# Batt_Op_Amp.net
KiCad netlist of a schematic drawn in Altium Designer
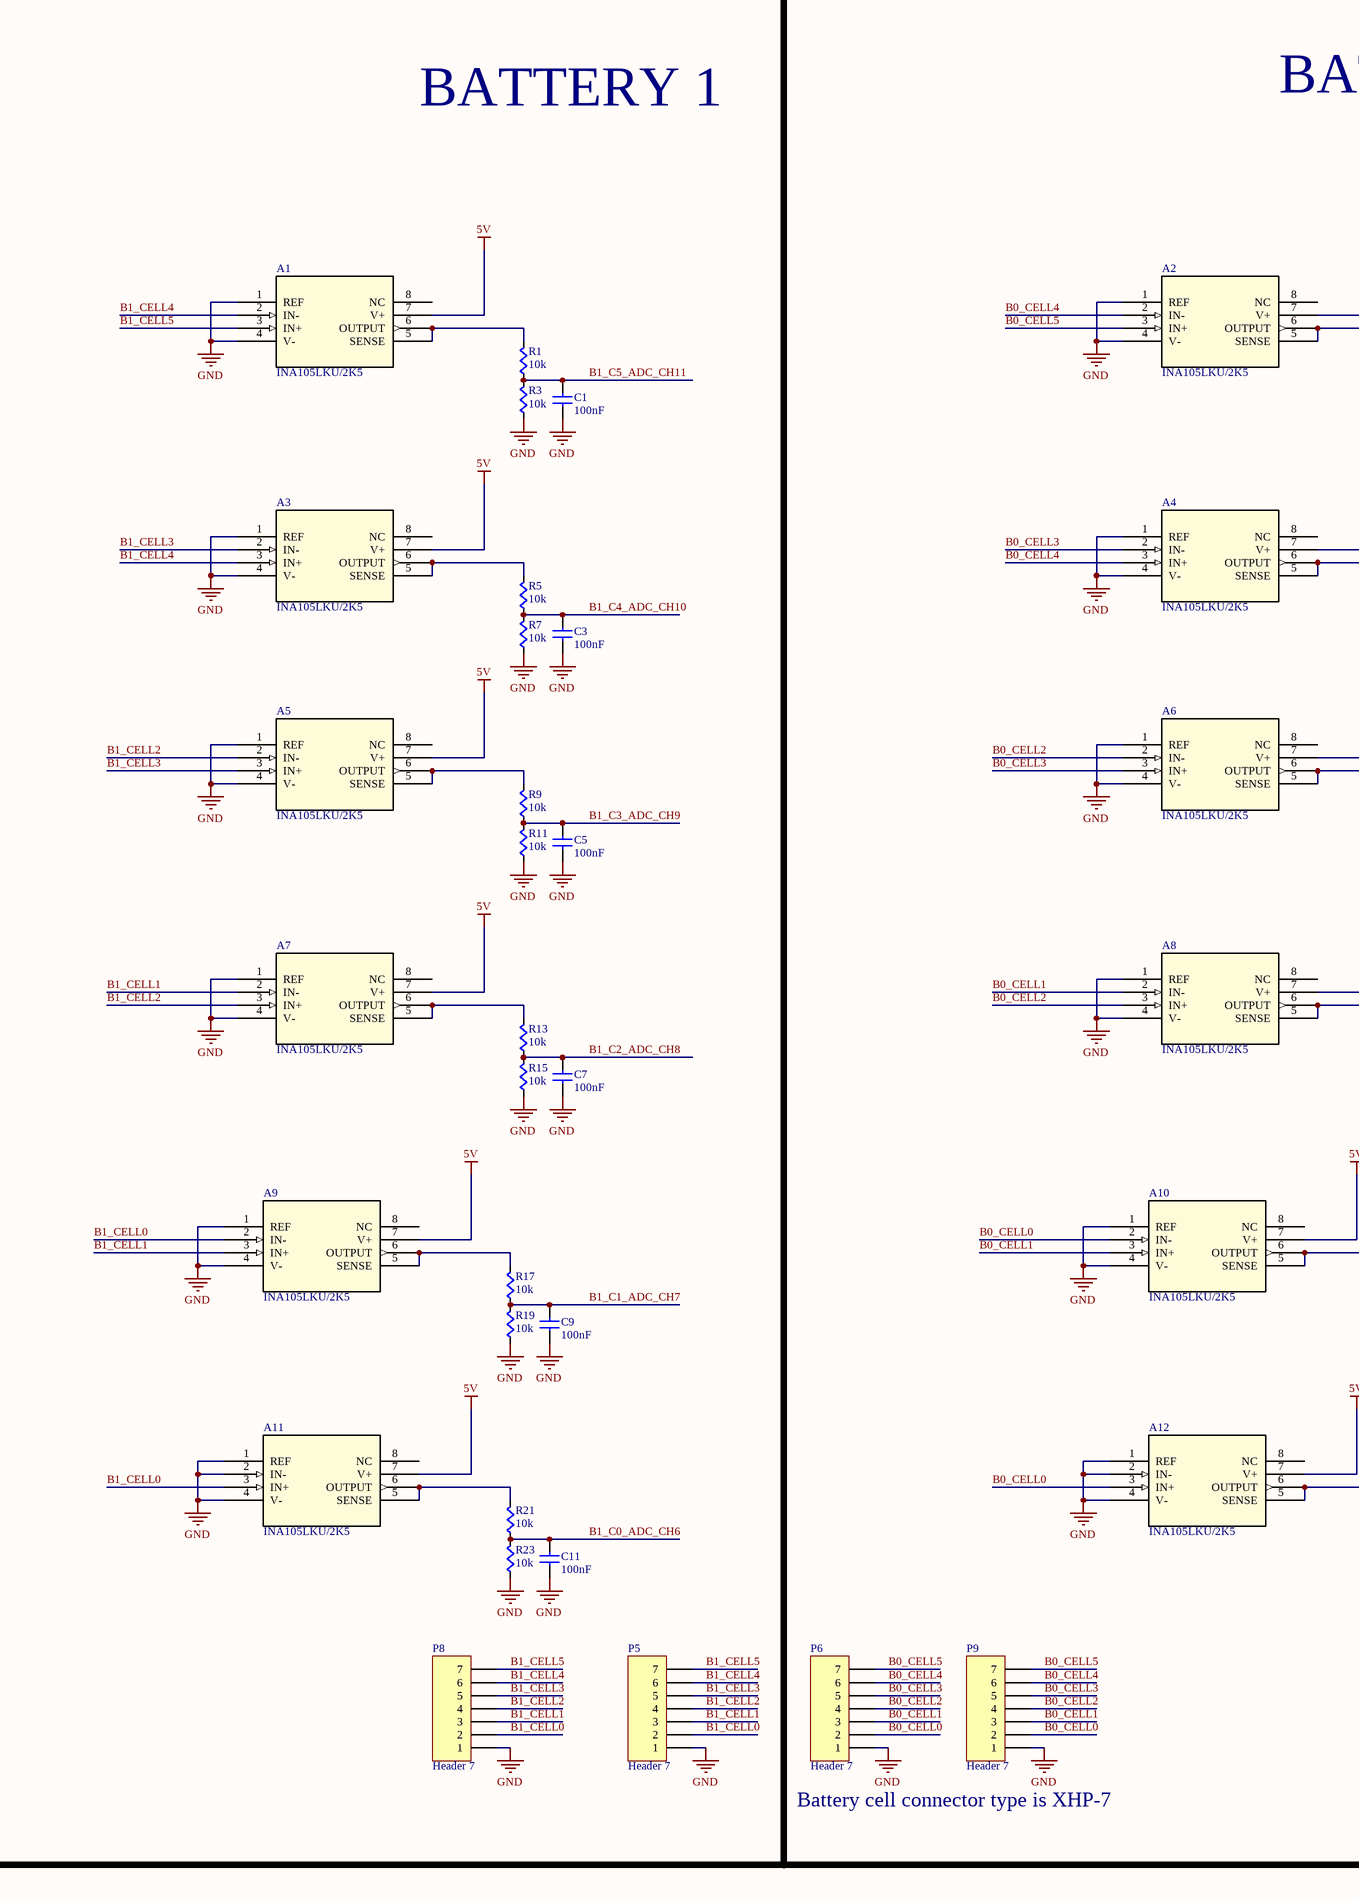
[diagram p0: Batt_Op_Amp.SchDoc, left]
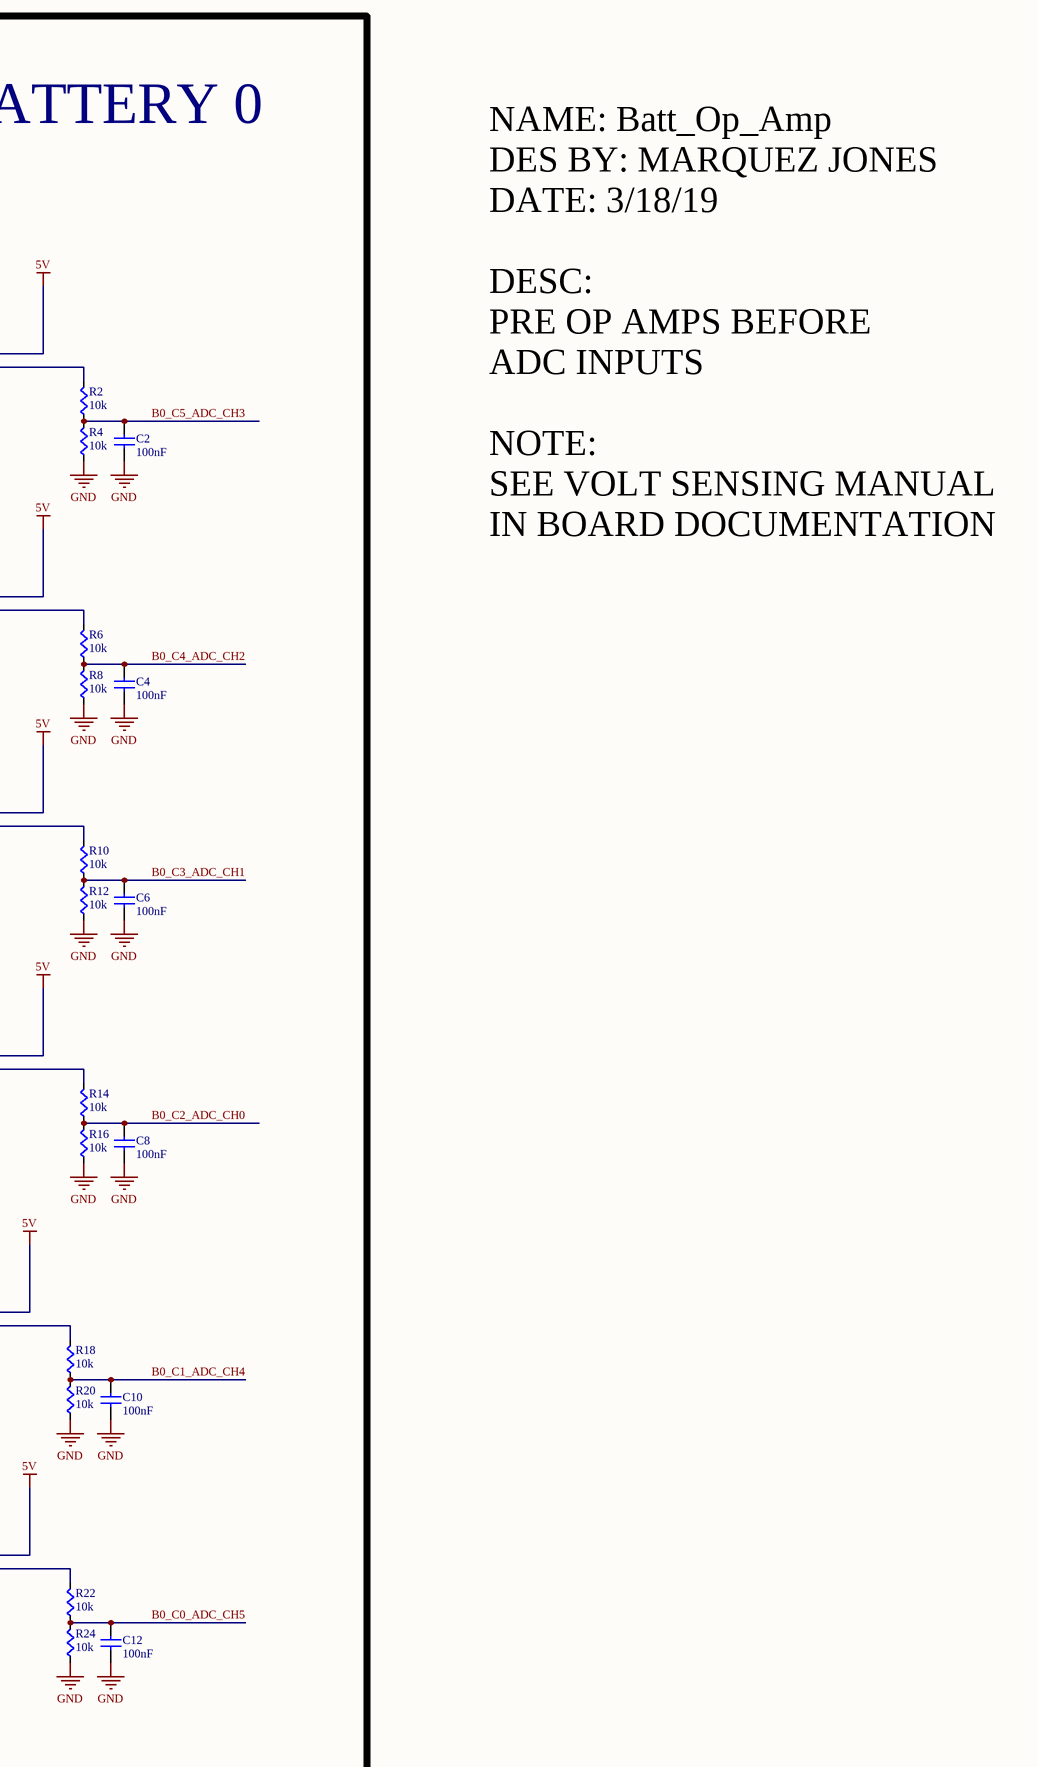
[diagram p1: Batt_Op_Amp.SchDoc, right]

(export (version "E")
  (design (tool "Eeschema 10.0.6"))
  (components
    (comp (ref "A1")
      (value "INA105LKU/2K5")
      (footprint "SOIC-8N")
      (libsource (lib "ICs") (part "INA105LKU/2K5"))
    )
    (comp (ref "A2")
      (value "INA105LKU/2K5")
      (footprint "SOIC-8N")
      (libsource (lib "ICs") (part "INA105LKU/2K5"))
    )
    (comp (ref "A3")
      (value "INA105LKU/2K5")
      (footprint "SOIC-8N")
      (libsource (lib "ICs") (part "INA105LKU/2K5"))
    )
    (comp (ref "A4")
      (value "INA105LKU/2K5")
      (footprint "SOIC-8N")
      (libsource (lib "ICs") (part "INA105LKU/2K5"))
    )
    (comp (ref "A5")
      (value "INA105LKU/2K5")
      (footprint "SOIC-8N")
      (libsource (lib "ICs") (part "INA105LKU/2K5"))
    )
    (comp (ref "A6")
      (value "INA105LKU/2K5")
      (footprint "SOIC-8N")
      (libsource (lib "ICs") (part "INA105LKU/2K5"))
    )
    (comp (ref "A7")
      (value "INA105LKU/2K5")
      (footprint "SOIC-8N")
      (libsource (lib "ICs") (part "INA105LKU/2K5"))
    )
    (comp (ref "A8")
      (value "INA105LKU/2K5")
      (footprint "SOIC-8N")
      (libsource (lib "ICs") (part "INA105LKU/2K5"))
    )
    (comp (ref "A9")
      (value "INA105LKU/2K5")
      (footprint "SOIC-8N")
      (libsource (lib "ICs") (part "INA105LKU/2K5"))
    )
    (comp (ref "A10")
      (value "INA105LKU/2K5")
      (footprint "SOIC-8N")
      (libsource (lib "ICs") (part "INA105LKU/2K5"))
    )
    (comp (ref "A11")
      (value "INA105LKU/2K5")
      (footprint "SOIC-8N")
      (libsource (lib "ICs") (part "INA105LKU/2K5"))
    )
    (comp (ref "A12")
      (value "INA105LKU/2K5")
      (footprint "SOIC-8N")
      (libsource (lib "ICs") (part "INA105LKU/2K5"))
    )
    (comp (ref "C1")
      (value "100nF")
      (footprint "CAPC0603")
      (fields (field (name "Comment") "Cap"))
      (libsource (lib "Passives") (part "Cap"))
    )
    (comp (ref "C2")
      (value "100nF")
      (footprint "CAPC0603")
      (fields (field (name "Comment") "Cap"))
      (libsource (lib "Passives") (part "Cap"))
    )
    (comp (ref "C3")
      (value "100nF")
      (footprint "CAPC0603")
      (fields (field (name "Comment") "Cap"))
      (libsource (lib "Passives") (part "Cap"))
    )
    (comp (ref "C4")
      (value "100nF")
      (footprint "CAPC0603")
      (fields (field (name "Comment") "Cap"))
      (libsource (lib "Passives") (part "Cap"))
    )
    (comp (ref "C5")
      (value "100nF")
      (footprint "CAPC0603")
      (fields (field (name "Comment") "Cap"))
      (libsource (lib "Passives") (part "Cap"))
    )
    (comp (ref "C6")
      (value "100nF")
      (footprint "CAPC0603")
      (fields (field (name "Comment") "Cap"))
      (libsource (lib "Passives") (part "Cap"))
    )
    (comp (ref "C7")
      (value "100nF")
      (footprint "CAPC0603")
      (fields (field (name "Comment") "Cap"))
      (libsource (lib "Passives") (part "Cap"))
    )
    (comp (ref "C8")
      (value "100nF")
      (footprint "CAPC0603")
      (fields (field (name "Comment") "Cap"))
      (libsource (lib "Passives") (part "Cap"))
    )
    (comp (ref "C9")
      (value "100nF")
      (footprint "CAPC0603")
      (fields (field (name "Comment") "Cap"))
      (libsource (lib "Passives") (part "Cap"))
    )
    (comp (ref "C10")
      (value "100nF")
      (footprint "CAPC0603")
      (fields (field (name "Comment") "Cap"))
      (libsource (lib "Passives") (part "Cap"))
    )
    (comp (ref "C11")
      (value "100nF")
      (footprint "CAPC0603")
      (fields (field (name "Comment") "Cap"))
      (libsource (lib "Passives") (part "Cap"))
    )
    (comp (ref "C12")
      (value "100nF")
      (footprint "CAPC0603")
      (fields (field (name "Comment") "Cap"))
      (libsource (lib "Passives") (part "Cap"))
    )
    (comp (ref "P5")
      (value "Header 7")
      (footprint "HDR1X7")
      (description "Header, 7-Pin")
      (fields (field (name "PUBLISHER") "Altium Limited"))
      (libsource (lib "Miscellaneous Connectors") (part "Header 7"))
    )
    (comp (ref "P6")
      (value "Header 7")
      (footprint "HDR1X7")
      (description "Header, 7-Pin")
      (fields (field (name "PUBLISHER") "Altium Limited"))
      (libsource (lib "Miscellaneous Connectors") (part "Header 7"))
    )
    (comp (ref "P8")
      (value "Header 7")
      (footprint "HDR1X7")
      (description "Header, 7-Pin")
      (fields (field (name "PUBLISHER") "Altium Limited"))
      (libsource (lib "Miscellaneous Connectors") (part "Header 7"))
    )
    (comp (ref "P9")
      (value "Header 7")
      (footprint "HDR1X7")
      (description "Header, 7-Pin")
      (fields (field (name "PUBLISHER") "Altium Limited"))
      (libsource (lib "Miscellaneous Connectors") (part "Header 7"))
    )
    (comp (ref "R1")
      (value "10k")
      (footprint "RES0603")
      (fields (field (name "Comment") "Res"))
      (libsource (lib "Passives") (part "Res"))
    )
    (comp (ref "R2")
      (value "10k")
      (footprint "RES0603")
      (fields (field (name "Comment") "Res"))
      (libsource (lib "Passives") (part "Res"))
    )
    (comp (ref "R3")
      (value "10k")
      (footprint "RES0603")
      (fields (field (name "Comment") "Res"))
      (libsource (lib "Passives") (part "Res"))
    )
    (comp (ref "R4")
      (value "10k")
      (footprint "RES0603")
      (fields (field (name "Comment") "Res"))
      (libsource (lib "Passives") (part "Res"))
    )
    (comp (ref "R5")
      (value "10k")
      (footprint "RES0603")
      (fields (field (name "Comment") "Res"))
      (libsource (lib "Passives") (part "Res"))
    )
    (comp (ref "R6")
      (value "10k")
      (footprint "RES0603")
      (fields (field (name "Comment") "Res"))
      (libsource (lib "Passives") (part "Res"))
    )
    (comp (ref "R7")
      (value "10k")
      (footprint "RES0603")
      (fields (field (name "Comment") "Res"))
      (libsource (lib "Passives") (part "Res"))
    )
    (comp (ref "R8")
      (value "10k")
      (footprint "RES0603")
      (fields (field (name "Comment") "Res"))
      (libsource (lib "Passives") (part "Res"))
    )
    (comp (ref "R9")
      (value "10k")
      (footprint "RES0603")
      (fields (field (name "Comment") "Res"))
      (libsource (lib "Passives") (part "Res"))
    )
    (comp (ref "R10")
      (value "10k")
      (footprint "RES0603")
      (fields (field (name "Comment") "Res"))
      (libsource (lib "Passives") (part "Res"))
    )
    (comp (ref "R11")
      (value "10k")
      (footprint "RES0603")
      (fields (field (name "Comment") "Res"))
      (libsource (lib "Passives") (part "Res"))
    )
    (comp (ref "R12")
      (value "10k")
      (footprint "RES0603")
      (fields (field (name "Comment") "Res"))
      (libsource (lib "Passives") (part "Res"))
    )
    (comp (ref "R13")
      (value "10k")
      (footprint "RES0603")
      (fields (field (name "Comment") "Res"))
      (libsource (lib "Passives") (part "Res"))
    )
    (comp (ref "R14")
      (value "10k")
      (footprint "RES0603")
      (fields (field (name "Comment") "Res"))
      (libsource (lib "Passives") (part "Res"))
    )
    (comp (ref "R15")
      (value "10k")
      (footprint "RES0603")
      (fields (field (name "Comment") "Res"))
      (libsource (lib "Passives") (part "Res"))
    )
    (comp (ref "R16")
      (value "10k")
      (footprint "RES0603")
      (fields (field (name "Comment") "Res"))
      (libsource (lib "Passives") (part "Res"))
    )
    (comp (ref "R17")
      (value "10k")
      (footprint "RES0603")
      (fields (field (name "Comment") "Res"))
      (libsource (lib "Passives") (part "Res"))
    )
    (comp (ref "R18")
      (value "10k")
      (footprint "RES0603")
      (fields (field (name "Comment") "Res"))
      (libsource (lib "Passives") (part "Res"))
    )
    (comp (ref "R19")
      (value "10k")
      (footprint "RES0603")
      (fields (field (name "Comment") "Res"))
      (libsource (lib "Passives") (part "Res"))
    )
    (comp (ref "R20")
      (value "10k")
      (footprint "RES0603")
      (fields (field (name "Comment") "Res"))
      (libsource (lib "Passives") (part "Res"))
    )
    (comp (ref "R21")
      (value "10k")
      (footprint "RES0603")
      (fields (field (name "Comment") "Res"))
      (libsource (lib "Passives") (part "Res"))
    )
    (comp (ref "R22")
      (value "10k")
      (footprint "RES0603")
      (fields (field (name "Comment") "Res"))
      (libsource (lib "Passives") (part "Res"))
    )
    (comp (ref "R23")
      (value "10k")
      (footprint "RES0603")
      (fields (field (name "Comment") "Res"))
      (libsource (lib "Passives") (part "Res"))
    )
    (comp (ref "R24")
      (value "10k")
      (footprint "RES0603")
      (fields (field (name "Comment") "Res"))
      (libsource (lib "Passives") (part "Res"))
    )
  )
  (nets
    (net (code "1") (name "/B0_C0_ADC_CH5") (class "Default")
      (node (ref "C12") (pin "1") (pinfunction "A_1") (pintype "passive"))
      (node (ref "R22") (pin "2") (pinfunction "B_2") (pintype "passive"))
      (node (ref "R24") (pin "1") (pinfunction "A_1") (pintype "passive"))
    )
    (net (code "2") (name "/B0_C1_ADC_CH4") (class "Default")
      (node (ref "C10") (pin "1") (pinfunction "A_1") (pintype "passive"))
      (node (ref "R18") (pin "2") (pinfunction "B_2") (pintype "passive"))
      (node (ref "R20") (pin "1") (pinfunction "A_1") (pintype "passive"))
    )
    (net (code "3") (name "/B0_C2_ADC_CH0") (class "Default")
      (node (ref "C8") (pin "1") (pinfunction "A_1") (pintype "passive"))
      (node (ref "R14") (pin "2") (pinfunction "B_2") (pintype "passive"))
      (node (ref "R16") (pin "1") (pinfunction "A_1") (pintype "passive"))
    )
    (net (code "4") (name "/B0_C3_ADC_CH1") (class "Default")
      (node (ref "C6") (pin "1") (pinfunction "A_1") (pintype "passive"))
      (node (ref "R10") (pin "2") (pinfunction "B_2") (pintype "passive"))
      (node (ref "R12") (pin "1") (pinfunction "A_1") (pintype "passive"))
    )
    (net (code "5") (name "/B0_C4_ADC_CH2") (class "Default")
      (node (ref "C4") (pin "1") (pinfunction "A_1") (pintype "passive"))
      (node (ref "R6") (pin "2") (pinfunction "B_2") (pintype "passive"))
      (node (ref "R8") (pin "1") (pinfunction "A_1") (pintype "passive"))
    )
    (net (code "6") (name "/B0_C5_ADC_CH3") (class "Default")
      (node (ref "C2") (pin "1") (pinfunction "A_1") (pintype "passive"))
      (node (ref "R2") (pin "2") (pinfunction "B_2") (pintype "passive"))
      (node (ref "R4") (pin "1") (pinfunction "A_1") (pintype "passive"))
    )
    (net (code "7") (name "/B0_CELL0") (class "Default")
      (node (ref "A10") (pin "2") (pinfunction "IN-_2") (pintype "input"))
      (node (ref "A12") (pin "3") (pinfunction "IN+_3") (pintype "input"))
      (node (ref "P6") (pin "2") (pinfunction "2_2") (pintype "passive"))
      (node (ref "P9") (pin "2") (pinfunction "2_2") (pintype "passive"))
    )
    (net (code "8") (name "/B0_CELL1") (class "Default")
      (node (ref "A10") (pin "3") (pinfunction "IN+_3") (pintype "input"))
      (node (ref "A8") (pin "2") (pinfunction "IN-_2") (pintype "input"))
      (node (ref "P6") (pin "3") (pinfunction "3_3") (pintype "passive"))
      (node (ref "P9") (pin "3") (pinfunction "3_3") (pintype "passive"))
    )
    (net (code "9") (name "/B0_CELL2") (class "Default")
      (node (ref "A6") (pin "2") (pinfunction "IN-_2") (pintype "input"))
      (node (ref "A8") (pin "3") (pinfunction "IN+_3") (pintype "input"))
      (node (ref "P6") (pin "4") (pinfunction "4_4") (pintype "passive"))
      (node (ref "P9") (pin "4") (pinfunction "4_4") (pintype "passive"))
    )
    (net (code "10") (name "/B0_CELL3") (class "Default")
      (node (ref "A4") (pin "2") (pinfunction "IN-_2") (pintype "input"))
      (node (ref "A6") (pin "3") (pinfunction "IN+_3") (pintype "input"))
      (node (ref "P6") (pin "5") (pinfunction "5_5") (pintype "passive"))
      (node (ref "P9") (pin "5") (pinfunction "5_5") (pintype "passive"))
    )
    (net (code "11") (name "/B0_CELL4") (class "Default")
      (node (ref "A2") (pin "2") (pinfunction "IN-_2") (pintype "input"))
      (node (ref "A4") (pin "3") (pinfunction "IN+_3") (pintype "input"))
      (node (ref "P6") (pin "6") (pinfunction "6_6") (pintype "passive"))
      (node (ref "P9") (pin "6") (pinfunction "6_6") (pintype "passive"))
    )
    (net (code "12") (name "/B0_CELL5") (class "Default")
      (node (ref "A2") (pin "3") (pinfunction "IN+_3") (pintype "input"))
      (node (ref "P6") (pin "7") (pinfunction "7_7") (pintype "passive"))
      (node (ref "P9") (pin "7") (pinfunction "7_7") (pintype "passive"))
    )
    (net (code "13") (name "/B1_C0_ADC_CH6") (class "Default")
      (node (ref "C11") (pin "1") (pinfunction "A_1") (pintype "passive"))
      (node (ref "R21") (pin "2") (pinfunction "B_2") (pintype "passive"))
      (node (ref "R23") (pin "1") (pinfunction "A_1") (pintype "passive"))
    )
    (net (code "14") (name "/B1_C1_ADC_CH7") (class "Default")
      (node (ref "C9") (pin "1") (pinfunction "A_1") (pintype "passive"))
      (node (ref "R17") (pin "2") (pinfunction "B_2") (pintype "passive"))
      (node (ref "R19") (pin "1") (pinfunction "A_1") (pintype "passive"))
    )
    (net (code "15") (name "/B1_C2_ADC_CH8") (class "Default")
      (node (ref "C7") (pin "1") (pinfunction "A_1") (pintype "passive"))
      (node (ref "R13") (pin "2") (pinfunction "B_2") (pintype "passive"))
      (node (ref "R15") (pin "1") (pinfunction "A_1") (pintype "passive"))
    )
    (net (code "16") (name "/B1_C3_ADC_CH9") (class "Default")
      (node (ref "C5") (pin "1") (pinfunction "A_1") (pintype "passive"))
      (node (ref "R11") (pin "1") (pinfunction "A_1") (pintype "passive"))
      (node (ref "R9") (pin "2") (pinfunction "B_2") (pintype "passive"))
    )
    (net (code "17") (name "/B1_C4_ADC_CH10") (class "Default")
      (node (ref "C3") (pin "1") (pinfunction "A_1") (pintype "passive"))
      (node (ref "R5") (pin "2") (pinfunction "B_2") (pintype "passive"))
      (node (ref "R7") (pin "1") (pinfunction "A_1") (pintype "passive"))
    )
    (net (code "18") (name "/B1_C5_ADC_CH11") (class "Default")
      (node (ref "C1") (pin "1") (pinfunction "A_1") (pintype "passive"))
      (node (ref "R1") (pin "2") (pinfunction "B_2") (pintype "passive"))
      (node (ref "R3") (pin "1") (pinfunction "A_1") (pintype "passive"))
    )
    (net (code "19") (name "/B1_CELL0") (class "Default")
      (node (ref "A11") (pin "3") (pinfunction "IN+_3") (pintype "input"))
      (node (ref "A9") (pin "2") (pinfunction "IN-_2") (pintype "input"))
      (node (ref "P5") (pin "2") (pinfunction "2_2") (pintype "passive"))
      (node (ref "P8") (pin "2") (pinfunction "2_2") (pintype "passive"))
    )
    (net (code "20") (name "/B1_CELL1") (class "Default")
      (node (ref "A7") (pin "2") (pinfunction "IN-_2") (pintype "input"))
      (node (ref "A9") (pin "3") (pinfunction "IN+_3") (pintype "input"))
      (node (ref "P5") (pin "3") (pinfunction "3_3") (pintype "passive"))
      (node (ref "P8") (pin "3") (pinfunction "3_3") (pintype "passive"))
    )
    (net (code "21") (name "/B1_CELL2") (class "Default")
      (node (ref "A5") (pin "2") (pinfunction "IN-_2") (pintype "input"))
      (node (ref "A7") (pin "3") (pinfunction "IN+_3") (pintype "input"))
      (node (ref "P5") (pin "4") (pinfunction "4_4") (pintype "passive"))
      (node (ref "P8") (pin "4") (pinfunction "4_4") (pintype "passive"))
    )
    (net (code "22") (name "/B1_CELL3") (class "Default")
      (node (ref "A3") (pin "2") (pinfunction "IN-_2") (pintype "input"))
      (node (ref "A5") (pin "3") (pinfunction "IN+_3") (pintype "input"))
      (node (ref "P5") (pin "5") (pinfunction "5_5") (pintype "passive"))
      (node (ref "P8") (pin "5") (pinfunction "5_5") (pintype "passive"))
    )
    (net (code "23") (name "/B1_CELL4") (class "Default")
      (node (ref "A1") (pin "2") (pinfunction "IN-_2") (pintype "input"))
      (node (ref "A3") (pin "3") (pinfunction "IN+_3") (pintype "input"))
      (node (ref "P5") (pin "6") (pinfunction "6_6") (pintype "passive"))
      (node (ref "P8") (pin "6") (pinfunction "6_6") (pintype "passive"))
    )
    (net (code "24") (name "/B1_CELL5") (class "Default")
      (node (ref "A1") (pin "3") (pinfunction "IN+_3") (pintype "input"))
      (node (ref "P5") (pin "7") (pinfunction "7_7") (pintype "passive"))
      (node (ref "P8") (pin "7") (pinfunction "7_7") (pintype "passive"))
    )
    (net (code "25") (name "5V") (class "Default")
      (node (ref "A1") (pin "7") (pinfunction "V+_7") (pintype "power_in"))
      (node (ref "A10") (pin "7") (pinfunction "V+_7") (pintype "power_in"))
      (node (ref "A11") (pin "7") (pinfunction "V+_7") (pintype "power_in"))
      (node (ref "A12") (pin "7") (pinfunction "V+_7") (pintype "power_in"))
      (node (ref "A2") (pin "7") (pinfunction "V+_7") (pintype "power_in"))
      (node (ref "A3") (pin "7") (pinfunction "V+_7") (pintype "power_in"))
      (node (ref "A4") (pin "7") (pinfunction "V+_7") (pintype "power_in"))
      (node (ref "A5") (pin "7") (pinfunction "V+_7") (pintype "power_in"))
      (node (ref "A6") (pin "7") (pinfunction "V+_7") (pintype "power_in"))
      (node (ref "A7") (pin "7") (pinfunction "V+_7") (pintype "power_in"))
      (node (ref "A8") (pin "7") (pinfunction "V+_7") (pintype "power_in"))
      (node (ref "A9") (pin "7") (pinfunction "V+_7") (pintype "power_in"))
    )
    (net (code "26") (name "GND") (class "Default")
      (node (ref "A1") (pin "1") (pinfunction "REF_1") (pintype "power_in"))
      (node (ref "A1") (pin "4") (pinfunction "V-_4") (pintype "power_in"))
      (node (ref "A10") (pin "1") (pinfunction "REF_1") (pintype "power_in"))
      (node (ref "A10") (pin "4") (pinfunction "V-_4") (pintype "power_in"))
      (node (ref "A11") (pin "1") (pinfunction "REF_1") (pintype "power_in"))
      (node (ref "A11") (pin "2") (pinfunction "IN-_2") (pintype "input"))
      (node (ref "A11") (pin "4") (pinfunction "V-_4") (pintype "power_in"))
      (node (ref "A12") (pin "1") (pinfunction "REF_1") (pintype "power_in"))
      (node (ref "A12") (pin "2") (pinfunction "IN-_2") (pintype "input"))
      (node (ref "A12") (pin "4") (pinfunction "V-_4") (pintype "power_in"))
      (node (ref "A2") (pin "1") (pinfunction "REF_1") (pintype "power_in"))
      (node (ref "A2") (pin "4") (pinfunction "V-_4") (pintype "power_in"))
      (node (ref "A3") (pin "1") (pinfunction "REF_1") (pintype "power_in"))
      (node (ref "A3") (pin "4") (pinfunction "V-_4") (pintype "power_in"))
      (node (ref "A4") (pin "1") (pinfunction "REF_1") (pintype "power_in"))
      (node (ref "A4") (pin "4") (pinfunction "V-_4") (pintype "power_in"))
      (node (ref "A5") (pin "1") (pinfunction "REF_1") (pintype "power_in"))
      (node (ref "A5") (pin "4") (pinfunction "V-_4") (pintype "power_in"))
      (node (ref "A6") (pin "1") (pinfunction "REF_1") (pintype "power_in"))
      (node (ref "A6") (pin "4") (pinfunction "V-_4") (pintype "power_in"))
      (node (ref "A7") (pin "1") (pinfunction "REF_1") (pintype "power_in"))
      (node (ref "A7") (pin "4") (pinfunction "V-_4") (pintype "power_in"))
      (node (ref "A8") (pin "1") (pinfunction "REF_1") (pintype "power_in"))
      (node (ref "A8") (pin "4") (pinfunction "V-_4") (pintype "power_in"))
      (node (ref "A9") (pin "1") (pinfunction "REF_1") (pintype "power_in"))
      (node (ref "A9") (pin "4") (pinfunction "V-_4") (pintype "power_in"))
      (node (ref "C1") (pin "2") (pinfunction "B_2") (pintype "passive"))
      (node (ref "C10") (pin "2") (pinfunction "B_2") (pintype "passive"))
      (node (ref "C11") (pin "2") (pinfunction "B_2") (pintype "passive"))
      (node (ref "C12") (pin "2") (pinfunction "B_2") (pintype "passive"))
      (node (ref "C2") (pin "2") (pinfunction "B_2") (pintype "passive"))
      (node (ref "C3") (pin "2") (pinfunction "B_2") (pintype "passive"))
      (node (ref "C4") (pin "2") (pinfunction "B_2") (pintype "passive"))
      (node (ref "C5") (pin "2") (pinfunction "B_2") (pintype "passive"))
      (node (ref "C6") (pin "2") (pinfunction "B_2") (pintype "passive"))
      (node (ref "C7") (pin "2") (pinfunction "B_2") (pintype "passive"))
      (node (ref "C8") (pin "2") (pinfunction "B_2") (pintype "passive"))
      (node (ref "C9") (pin "2") (pinfunction "B_2") (pintype "passive"))
      (node (ref "P5") (pin "1") (pinfunction "1_1") (pintype "passive"))
      (node (ref "P6") (pin "1") (pinfunction "1_1") (pintype "passive"))
      (node (ref "P8") (pin "1") (pinfunction "1_1") (pintype "passive"))
      (node (ref "P9") (pin "1") (pinfunction "1_1") (pintype "passive"))
      (node (ref "R11") (pin "2") (pinfunction "B_2") (pintype "passive"))
      (node (ref "R12") (pin "2") (pinfunction "B_2") (pintype "passive"))
      (node (ref "R15") (pin "2") (pinfunction "B_2") (pintype "passive"))
      (node (ref "R16") (pin "2") (pinfunction "B_2") (pintype "passive"))
      (node (ref "R19") (pin "2") (pinfunction "B_2") (pintype "passive"))
      (node (ref "R20") (pin "2") (pinfunction "B_2") (pintype "passive"))
      (node (ref "R23") (pin "2") (pinfunction "B_2") (pintype "passive"))
      (node (ref "R24") (pin "2") (pinfunction "B_2") (pintype "passive"))
      (node (ref "R3") (pin "2") (pinfunction "B_2") (pintype "passive"))
      (node (ref "R4") (pin "2") (pinfunction "B_2") (pintype "passive"))
      (node (ref "R7") (pin "2") (pinfunction "B_2") (pintype "passive"))
      (node (ref "R8") (pin "2") (pinfunction "B_2") (pintype "passive"))
    )
    (net (code "27") (name "Net-(A1-OUTPUT)") (class "Default")
      (node (ref "A1") (pin "5") (pinfunction "SENSE_5") (pintype "passive"))
      (node (ref "A1") (pin "6") (pinfunction "OUTPUT_6") (pintype "output"))
      (node (ref "R1") (pin "1") (pinfunction "A_1") (pintype "passive"))
    )
    (net (code "28") (name "Net-(A2-OUTPUT)") (class "Default")
      (node (ref "A2") (pin "5") (pinfunction "SENSE_5") (pintype "passive"))
      (node (ref "A2") (pin "6") (pinfunction "OUTPUT_6") (pintype "output"))
      (node (ref "R2") (pin "1") (pinfunction "A_1") (pintype "passive"))
    )
    (net (code "29") (name "Net-(A3-OUTPUT)") (class "Default")
      (node (ref "A3") (pin "5") (pinfunction "SENSE_5") (pintype "passive"))
      (node (ref "A3") (pin "6") (pinfunction "OUTPUT_6") (pintype "output"))
      (node (ref "R5") (pin "1") (pinfunction "A_1") (pintype "passive"))
    )
    (net (code "30") (name "Net-(A4-OUTPUT)") (class "Default")
      (node (ref "A4") (pin "5") (pinfunction "SENSE_5") (pintype "passive"))
      (node (ref "A4") (pin "6") (pinfunction "OUTPUT_6") (pintype "output"))
      (node (ref "R6") (pin "1") (pinfunction "A_1") (pintype "passive"))
    )
    (net (code "31") (name "Net-(A5-OUTPUT)") (class "Default")
      (node (ref "A5") (pin "5") (pinfunction "SENSE_5") (pintype "passive"))
      (node (ref "A5") (pin "6") (pinfunction "OUTPUT_6") (pintype "output"))
      (node (ref "R9") (pin "1") (pinfunction "A_1") (pintype "passive"))
    )
    (net (code "32") (name "Net-(A6-OUTPUT)") (class "Default")
      (node (ref "A6") (pin "5") (pinfunction "SENSE_5") (pintype "passive"))
      (node (ref "A6") (pin "6") (pinfunction "OUTPUT_6") (pintype "output"))
      (node (ref "R10") (pin "1") (pinfunction "A_1") (pintype "passive"))
    )
    (net (code "33") (name "Net-(A7-OUTPUT)") (class "Default")
      (node (ref "A7") (pin "5") (pinfunction "SENSE_5") (pintype "passive"))
      (node (ref "A7") (pin "6") (pinfunction "OUTPUT_6") (pintype "output"))
      (node (ref "R13") (pin "1") (pinfunction "A_1") (pintype "passive"))
    )
    (net (code "34") (name "Net-(A8-OUTPUT)") (class "Default")
      (node (ref "A8") (pin "5") (pinfunction "SENSE_5") (pintype "passive"))
      (node (ref "A8") (pin "6") (pinfunction "OUTPUT_6") (pintype "output"))
      (node (ref "R14") (pin "1") (pinfunction "A_1") (pintype "passive"))
    )
    (net (code "35") (name "Net-(A9-OUTPUT)") (class "Default")
      (node (ref "A9") (pin "5") (pinfunction "SENSE_5") (pintype "passive"))
      (node (ref "A9") (pin "6") (pinfunction "OUTPUT_6") (pintype "output"))
      (node (ref "R17") (pin "1") (pinfunction "A_1") (pintype "passive"))
    )
    (net (code "36") (name "Net-(A10-OUTPUT)") (class "Default")
      (node (ref "A10") (pin "5") (pinfunction "SENSE_5") (pintype "passive"))
      (node (ref "A10") (pin "6") (pinfunction "OUTPUT_6") (pintype "output"))
      (node (ref "R18") (pin "1") (pinfunction "A_1") (pintype "passive"))
    )
    (net (code "37") (name "Net-(A11-OUTPUT)") (class "Default")
      (node (ref "A11") (pin "5") (pinfunction "SENSE_5") (pintype "passive"))
      (node (ref "A11") (pin "6") (pinfunction "OUTPUT_6") (pintype "output"))
      (node (ref "R21") (pin "1") (pinfunction "A_1") (pintype "passive"))
    )
    (net (code "38") (name "Net-(A12-OUTPUT)") (class "Default")
      (node (ref "A12") (pin "5") (pinfunction "SENSE_5") (pintype "passive"))
      (node (ref "A12") (pin "6") (pinfunction "OUTPUT_6") (pintype "output"))
      (node (ref "R22") (pin "1") (pinfunction "A_1") (pintype "passive"))
    )
    (net (code "39") (name "unconnected-(A1-NC-Pad8)") (class "Default")
      (node (ref "A1") (pin "8") (pinfunction "NC_8") (pintype "passive"))
    )
    (net (code "40") (name "unconnected-(A2-NC-Pad8)") (class "Default")
      (node (ref "A2") (pin "8") (pinfunction "NC_8") (pintype "passive"))
    )
    (net (code "41") (name "unconnected-(A3-NC-Pad8)") (class "Default")
      (node (ref "A3") (pin "8") (pinfunction "NC_8") (pintype "passive"))
    )
    (net (code "42") (name "unconnected-(A4-NC-Pad8)") (class "Default")
      (node (ref "A4") (pin "8") (pinfunction "NC_8") (pintype "passive"))
    )
    (net (code "43") (name "unconnected-(A5-NC-Pad8)") (class "Default")
      (node (ref "A5") (pin "8") (pinfunction "NC_8") (pintype "passive"))
    )
    (net (code "44") (name "unconnected-(A6-NC-Pad8)") (class "Default")
      (node (ref "A6") (pin "8") (pinfunction "NC_8") (pintype "passive"))
    )
    (net (code "45") (name "unconnected-(A7-NC-Pad8)") (class "Default")
      (node (ref "A7") (pin "8") (pinfunction "NC_8") (pintype "passive"))
    )
    (net (code "46") (name "unconnected-(A8-NC-Pad8)") (class "Default")
      (node (ref "A8") (pin "8") (pinfunction "NC_8") (pintype "passive"))
    )
    (net (code "47") (name "unconnected-(A9-NC-Pad8)") (class "Default")
      (node (ref "A9") (pin "8") (pinfunction "NC_8") (pintype "passive"))
    )
    (net (code "48") (name "unconnected-(A10-NC-Pad8)") (class "Default")
      (node (ref "A10") (pin "8") (pinfunction "NC_8") (pintype "passive"))
    )
    (net (code "49") (name "unconnected-(A11-NC-Pad8)") (class "Default")
      (node (ref "A11") (pin "8") (pinfunction "NC_8") (pintype "passive"))
    )
    (net (code "50") (name "unconnected-(A12-NC-Pad8)") (class "Default")
      (node (ref "A12") (pin "8") (pinfunction "NC_8") (pintype "passive"))
    )
  )
)
